# Seilwinde.net
KiCad netlist of a schematic drawn in EAGLE
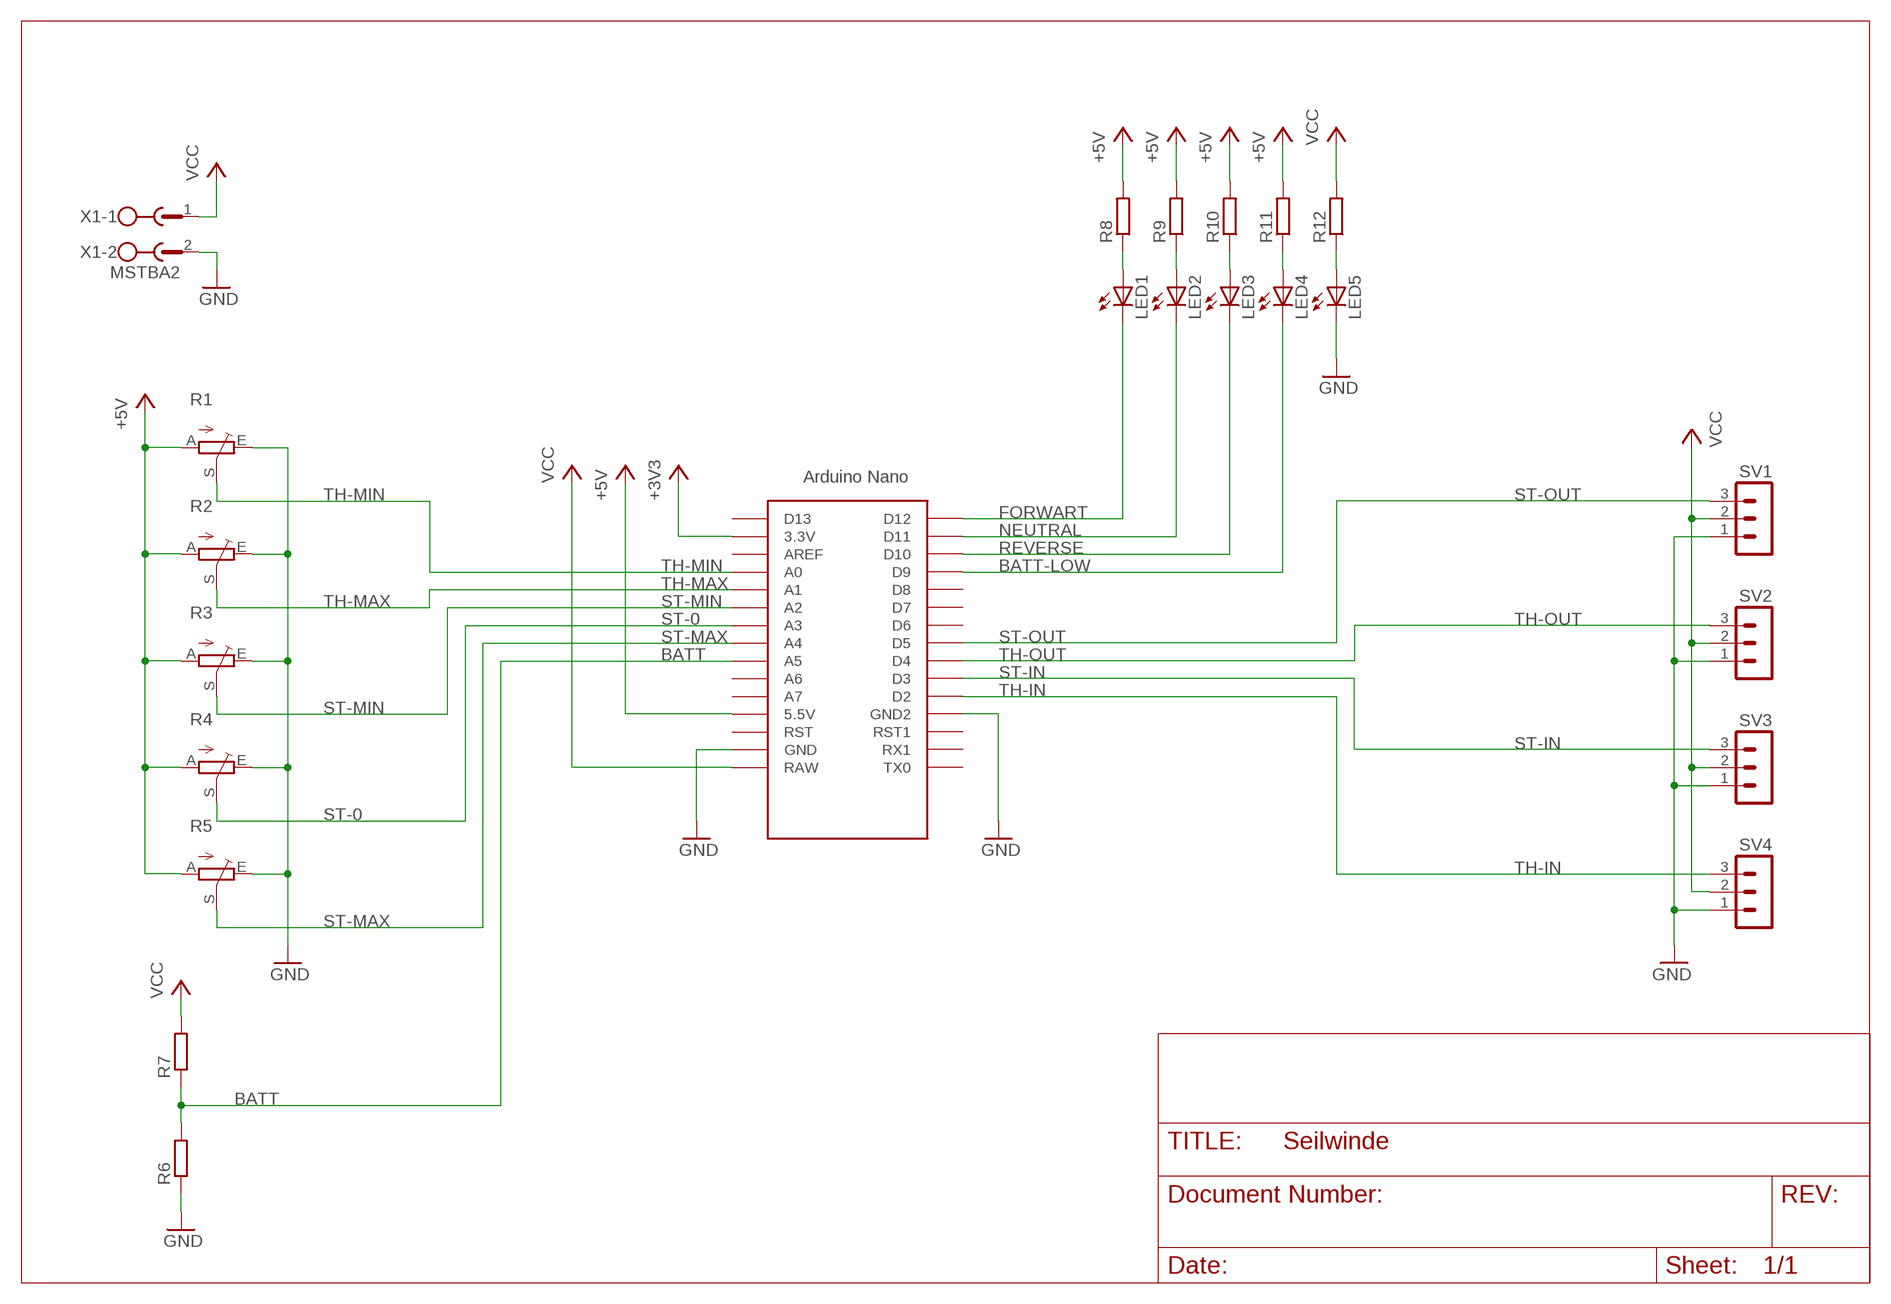
[diagram p0: schematic, sheet 1]

(export (version "E")
  (design (tool "Eeschema 10.0.6"))
  (components
    (comp (ref "LED1")
      (value "LEDCHIPLED_1206")
      (footprint "eagle-import:CHIPLED_1206")
      (libsource (lib "eagle-import") (part "LEDCHIPLED_1206"))
    )
    (comp (ref "LED2")
      (value "LEDCHIPLED_1206")
      (footprint "eagle-import:CHIPLED_1206")
      (libsource (lib "eagle-import") (part "LEDCHIPLED_1206"))
    )
    (comp (ref "LED3")
      (value "LEDCHIPLED_1206")
      (footprint "eagle-import:CHIPLED_1206")
      (libsource (lib "eagle-import") (part "LEDCHIPLED_1206"))
    )
    (comp (ref "LED4")
      (value "LEDCHIPLED_1206")
      (footprint "eagle-import:CHIPLED_1206")
      (libsource (lib "eagle-import") (part "LEDCHIPLED_1206"))
    )
    (comp (ref "LED5")
      (value "LEDCHIPLED_1206")
      (footprint "eagle-import:CHIPLED_1206")
      (libsource (lib "eagle-import") (part "LEDCHIPLED_1206"))
    )
    (comp (ref "R1")
      (value "TRIM_EU-S64W")
      (footprint "eagle-import:S64W")
      (libsource (lib "eagle-import") (part "TRIM_EU-S64W"))
    )
    (comp (ref "R2")
      (value "TRIM_EU-S64W")
      (footprint "eagle-import:S64W")
      (libsource (lib "eagle-import") (part "TRIM_EU-S64W"))
    )
    (comp (ref "R3")
      (value "TRIM_EU-S64W")
      (footprint "eagle-import:S64W")
      (libsource (lib "eagle-import") (part "TRIM_EU-S64W"))
    )
    (comp (ref "R4")
      (value "TRIM_EU-S64W")
      (footprint "eagle-import:S64W")
      (libsource (lib "eagle-import") (part "TRIM_EU-S64W"))
    )
    (comp (ref "R5")
      (value "TRIM_EU-S64W")
      (footprint "eagle-import:S64W")
      (libsource (lib "eagle-import") (part "TRIM_EU-S64W"))
    )
    (comp (ref "R6")
      (value "R-EU_R1206")
      (footprint "eagle-import:R1206")
      (libsource (lib "eagle-import") (part "R-EU_R1206"))
    )
    (comp (ref "R7")
      (value "R-EU_R1206")
      (footprint "eagle-import:R1206")
      (libsource (lib "eagle-import") (part "R-EU_R1206"))
    )
    (comp (ref "R8")
      (value "R-EU_R1206")
      (footprint "eagle-import:R1206")
      (libsource (lib "eagle-import") (part "R-EU_R1206"))
    )
    (comp (ref "R9")
      (value "R-EU_R1206")
      (footprint "eagle-import:R1206")
      (libsource (lib "eagle-import") (part "R-EU_R1206"))
    )
    (comp (ref "R10")
      (value "R-EU_R1206")
      (footprint "eagle-import:R1206")
      (libsource (lib "eagle-import") (part "R-EU_R1206"))
    )
    (comp (ref "R11")
      (value "R-EU_R1206")
      (footprint "eagle-import:R1206")
      (libsource (lib "eagle-import") (part "R-EU_R1206"))
    )
    (comp (ref "R12")
      (value "R-EU_R1206")
      (footprint "eagle-import:R1206")
      (libsource (lib "eagle-import") (part "R-EU_R1206"))
    )
    (comp (ref "SV1")
      (value "MA03-1")
      (footprint "eagle-import:MA03-1")
      (libsource (lib "eagle-import") (part "MA03-1"))
    )
    (comp (ref "SV2")
      (value "MA03-1")
      (footprint "eagle-import:MA03-1")
      (libsource (lib "eagle-import") (part "MA03-1"))
    )
    (comp (ref "SV3")
      (value "MA03-1")
      (footprint "eagle-import:MA03-1")
      (libsource (lib "eagle-import") (part "MA03-1"))
    )
    (comp (ref "SV4")
      (value "MA03-1")
      (footprint "eagle-import:MA03-1")
      (libsource (lib "eagle-import") (part "MA03-1"))
    )
    (comp (ref "U$1")
      (value "NANO")
      (footprint "eagle-import:NANO")
      (libsource (lib "eagle-import") (part "NANO"))
    )
    (comp (ref "X1")
      (value "MSTBA2")
      (footprint "eagle-import:MSTBA2")
      (fields (field (name "MF") "FARNELL") (field (name "MPN") "1757242"))
      (libsource (lib "eagle-import") (part "MSTBA2"))
    )
  )
  (nets
    (net (code "1") (name "+3V3") (class "Default")
      (node (ref "U$1") (pin "3.3V") (pinfunction "3.3V_3.3V") (pintype "bidirectional"))
    )
    (net (code "2") (name "+5V") (class "Default")
      (node (ref "R1") (pin "A") (pinfunction "A_A") (pintype "passive"))
      (node (ref "R10") (pin "2") (pinfunction "2_2") (pintype "passive"))
      (node (ref "R11") (pin "2") (pinfunction "2_2") (pintype "passive"))
      (node (ref "R2") (pin "A") (pinfunction "A_A") (pintype "passive"))
      (node (ref "R3") (pin "A") (pinfunction "A_A") (pintype "passive"))
      (node (ref "R4") (pin "A") (pinfunction "A_A") (pintype "passive"))
      (node (ref "R5") (pin "A") (pinfunction "A_A") (pintype "passive"))
      (node (ref "R8") (pin "2") (pinfunction "2_2") (pintype "passive"))
      (node (ref "R9") (pin "2") (pinfunction "2_2") (pintype "passive"))
      (node (ref "U$1") (pin "5V") (pinfunction "5.5V_5V") (pintype "bidirectional"))
    )
    (net (code "3") (name "/BATT") (class "Default")
      (node (ref "R6") (pin "2") (pinfunction "2_2") (pintype "passive"))
      (node (ref "R7") (pin "1") (pinfunction "1_1") (pintype "passive"))
      (node (ref "U$1") (pin "A5") (pinfunction "A5_A5") (pintype "bidirectional"))
    )
    (net (code "4") (name "/BATT-LOW") (class "Default")
      (node (ref "LED4") (pin "C") (pinfunction "C_C") (pintype "passive"))
      (node (ref "U$1") (pin "D9") (pinfunction "D9_D9") (pintype "bidirectional"))
    )
    (net (code "5") (name "/FORWART") (class "Default")
      (node (ref "LED1") (pin "C") (pinfunction "C_C") (pintype "passive"))
      (node (ref "U$1") (pin "D12") (pinfunction "D12_D12") (pintype "bidirectional"))
    )
    (net (code "6") (name "/NEUTRAL") (class "Default")
      (node (ref "LED2") (pin "C") (pinfunction "C_C") (pintype "passive"))
      (node (ref "U$1") (pin "D11") (pinfunction "D11_D11") (pintype "bidirectional"))
    )
    (net (code "7") (name "/REVERSE") (class "Default")
      (node (ref "LED3") (pin "C") (pinfunction "C_C") (pintype "passive"))
      (node (ref "U$1") (pin "D10") (pinfunction "D10_D10") (pintype "bidirectional"))
    )
    (net (code "8") (name "/ST-0") (class "Default")
      (node (ref "R4") (pin "S") (pinfunction "S_S") (pintype "passive"))
      (node (ref "U$1") (pin "A3") (pinfunction "A3_A3") (pintype "bidirectional"))
    )
    (net (code "9") (name "/ST-IN") (class "Default")
      (node (ref "SV3") (pin "3") (pinfunction "3_3") (pintype "passive"))
      (node (ref "U$1") (pin "D3") (pinfunction "D3_D3") (pintype "bidirectional"))
    )
    (net (code "10") (name "/ST-MAX") (class "Default")
      (node (ref "R5") (pin "S") (pinfunction "S_S") (pintype "passive"))
      (node (ref "U$1") (pin "A4") (pinfunction "A4_A4") (pintype "bidirectional"))
    )
    (net (code "11") (name "/ST-MIN") (class "Default")
      (node (ref "R3") (pin "S") (pinfunction "S_S") (pintype "passive"))
      (node (ref "U$1") (pin "A2") (pinfunction "A2_A2") (pintype "bidirectional"))
    )
    (net (code "12") (name "/ST-OUT") (class "Default")
      (node (ref "SV1") (pin "3") (pinfunction "3_3") (pintype "passive"))
      (node (ref "U$1") (pin "D5") (pinfunction "D5_D5") (pintype "bidirectional"))
    )
    (net (code "13") (name "/TH-IN") (class "Default")
      (node (ref "SV4") (pin "3") (pinfunction "3_3") (pintype "passive"))
      (node (ref "U$1") (pin "D2") (pinfunction "D2_D2") (pintype "bidirectional"))
    )
    (net (code "14") (name "/TH-MAX") (class "Default")
      (node (ref "R2") (pin "S") (pinfunction "S_S") (pintype "passive"))
      (node (ref "U$1") (pin "A1") (pinfunction "A1_A1") (pintype "bidirectional"))
    )
    (net (code "15") (name "/TH-MIN") (class "Default")
      (node (ref "R1") (pin "S") (pinfunction "S_S") (pintype "passive"))
      (node (ref "U$1") (pin "A0") (pinfunction "A0_A0") (pintype "bidirectional"))
    )
    (net (code "16") (name "/TH-OUT") (class "Default")
      (node (ref "SV2") (pin "3") (pinfunction "3_3") (pintype "passive"))
      (node (ref "U$1") (pin "D4") (pinfunction "D4_D4") (pintype "bidirectional"))
    )
    (net (code "17") (name "GND") (class "Default")
      (node (ref "LED5") (pin "C") (pinfunction "C_C") (pintype "passive"))
      (node (ref "R1") (pin "E") (pinfunction "E_E") (pintype "passive"))
      (node (ref "R2") (pin "E") (pinfunction "E_E") (pintype "passive"))
      (node (ref "R3") (pin "E") (pinfunction "E_E") (pintype "passive"))
      (node (ref "R4") (pin "E") (pinfunction "E_E") (pintype "passive"))
      (node (ref "R5") (pin "E") (pinfunction "E_E") (pintype "passive"))
      (node (ref "R6") (pin "1") (pinfunction "1_1") (pintype "passive"))
      (node (ref "SV1") (pin "1") (pinfunction "1_1") (pintype "passive"))
      (node (ref "SV2") (pin "1") (pinfunction "1_1") (pintype "passive"))
      (node (ref "SV3") (pin "1") (pinfunction "1_1") (pintype "passive"))
      (node (ref "SV4") (pin "1") (pinfunction "1_1") (pintype "passive"))
      (node (ref "U$1") (pin "GND") (pinfunction "GND_GND") (pintype "bidirectional"))
      (node (ref "U$1") (pin "GND1") (pinfunction "GND2_GND1") (pintype "bidirectional"))
      (node (ref "X1") (pin "2") (pinfunction "1_2") (pintype "passive"))
    )
    (net (code "18") (name "Net-(LED1-PadA)") (class "Default")
      (node (ref "LED1") (pin "A") (pinfunction "A_A") (pintype "passive"))
      (node (ref "R8") (pin "1") (pinfunction "1_1") (pintype "passive"))
    )
    (net (code "19") (name "Net-(LED2-PadA)") (class "Default")
      (node (ref "LED2") (pin "A") (pinfunction "A_A") (pintype "passive"))
      (node (ref "R9") (pin "1") (pinfunction "1_1") (pintype "passive"))
    )
    (net (code "20") (name "Net-(LED3-PadA)") (class "Default")
      (node (ref "LED3") (pin "A") (pinfunction "A_A") (pintype "passive"))
      (node (ref "R10") (pin "1") (pinfunction "1_1") (pintype "passive"))
    )
    (net (code "21") (name "Net-(LED4-PadA)") (class "Default")
      (node (ref "LED4") (pin "A") (pinfunction "A_A") (pintype "passive"))
      (node (ref "R11") (pin "1") (pinfunction "1_1") (pintype "passive"))
    )
    (net (code "22") (name "Net-(LED5-PadA)") (class "Default")
      (node (ref "LED5") (pin "A") (pinfunction "A_A") (pintype "passive"))
      (node (ref "R12") (pin "1") (pinfunction "1_1") (pintype "passive"))
    )
    (net (code "23") (name "VCC") (class "Default")
      (node (ref "R12") (pin "2") (pinfunction "2_2") (pintype "passive"))
      (node (ref "R7") (pin "2") (pinfunction "2_2") (pintype "passive"))
      (node (ref "SV1") (pin "2") (pinfunction "2_2") (pintype "passive"))
      (node (ref "SV2") (pin "2") (pinfunction "2_2") (pintype "passive"))
      (node (ref "SV3") (pin "2") (pinfunction "2_2") (pintype "passive"))
      (node (ref "SV4") (pin "2") (pinfunction "2_2") (pintype "passive"))
      (node (ref "U$1") (pin "RAW") (pinfunction "RAW_RAW") (pintype "bidirectional"))
      (node (ref "X1") (pin "1") (pinfunction "1_1") (pintype "passive"))
    )
    (net (code "24") (name "unconnected-(U$1-PadA6)") (class "Default")
      (node (ref "U$1") (pin "A6") (pinfunction "A6_A6") (pintype "bidirectional"))
    )
    (net (code "25") (name "unconnected-(U$1-PadA7)") (class "Default")
      (node (ref "U$1") (pin "A7") (pinfunction "A7_A7") (pintype "bidirectional"))
    )
    (net (code "26") (name "unconnected-(U$1-PadAREF)") (class "Default")
      (node (ref "U$1") (pin "AREF") (pinfunction "AREF_AREF") (pintype "bidirectional"))
    )
    (net (code "27") (name "unconnected-(U$1-PadD6)") (class "Default")
      (node (ref "U$1") (pin "D6") (pinfunction "D6_D6") (pintype "bidirectional"))
    )
    (net (code "28") (name "unconnected-(U$1-PadD7)") (class "Default")
      (node (ref "U$1") (pin "D7") (pinfunction "D7_D7") (pintype "bidirectional"))
    )
    (net (code "29") (name "unconnected-(U$1-PadD8)") (class "Default")
      (node (ref "U$1") (pin "D8") (pinfunction "D8_D8") (pintype "bidirectional"))
    )
    (net (code "30") (name "unconnected-(U$1-PadD13)") (class "Default")
      (node (ref "U$1") (pin "D13") (pinfunction "D13_D13") (pintype "bidirectional"))
    )
    (net (code "31") (name "unconnected-(U$1-PadICSP1)") (class "Default")
      (node (ref "U$1") (pin "ICSP1") (pinfunction "ICSP1_ICSP1") (pintype "bidirectional"))
    )
    (net (code "32") (name "unconnected-(U$1-PadICSP2)") (class "Default")
      (node (ref "U$1") (pin "ICSP2") (pinfunction "ICSP2_ICSP2") (pintype "bidirectional"))
    )
    (net (code "33") (name "unconnected-(U$1-PadICSP3)") (class "Default")
      (node (ref "U$1") (pin "ICSP3") (pinfunction "ICSP3_ICSP3") (pintype "bidirectional"))
    )
    (net (code "34") (name "unconnected-(U$1-PadICSP4)") (class "Default")
      (node (ref "U$1") (pin "ICSP4") (pinfunction "ICSP4_ICSP4") (pintype "bidirectional"))
    )
    (net (code "35") (name "unconnected-(U$1-PadICSP5)") (class "Default")
      (node (ref "U$1") (pin "ICSP5") (pinfunction "ICSP5_ICSP5") (pintype "bidirectional"))
    )
    (net (code "36") (name "unconnected-(U$1-PadICSP6)") (class "Default")
      (node (ref "U$1") (pin "ICSP6") (pinfunction "ICSP6_ICSP6") (pintype "bidirectional"))
    )
    (net (code "37") (name "unconnected-(U$1-PadRST)") (class "Default")
      (node (ref "U$1") (pin "RST") (pinfunction "RST_RST") (pintype "bidirectional"))
    )
    (net (code "38") (name "unconnected-(U$1-PadRST1)") (class "Default")
      (node (ref "U$1") (pin "RST1") (pinfunction "RST1_RST1") (pintype "bidirectional"))
    )
    (net (code "39") (name "unconnected-(U$1-PadRX1)") (class "Default")
      (node (ref "U$1") (pin "RX1") (pinfunction "RX1_RX1") (pintype "bidirectional"))
    )
    (net (code "40") (name "unconnected-(U$1-PadTX0)") (class "Default")
      (node (ref "U$1") (pin "TX0") (pinfunction "TX0_TX0") (pintype "bidirectional"))
    )
  )
)
